# BMS_STM32.net
KiCad netlist of a schematic drawn in Altium Designer
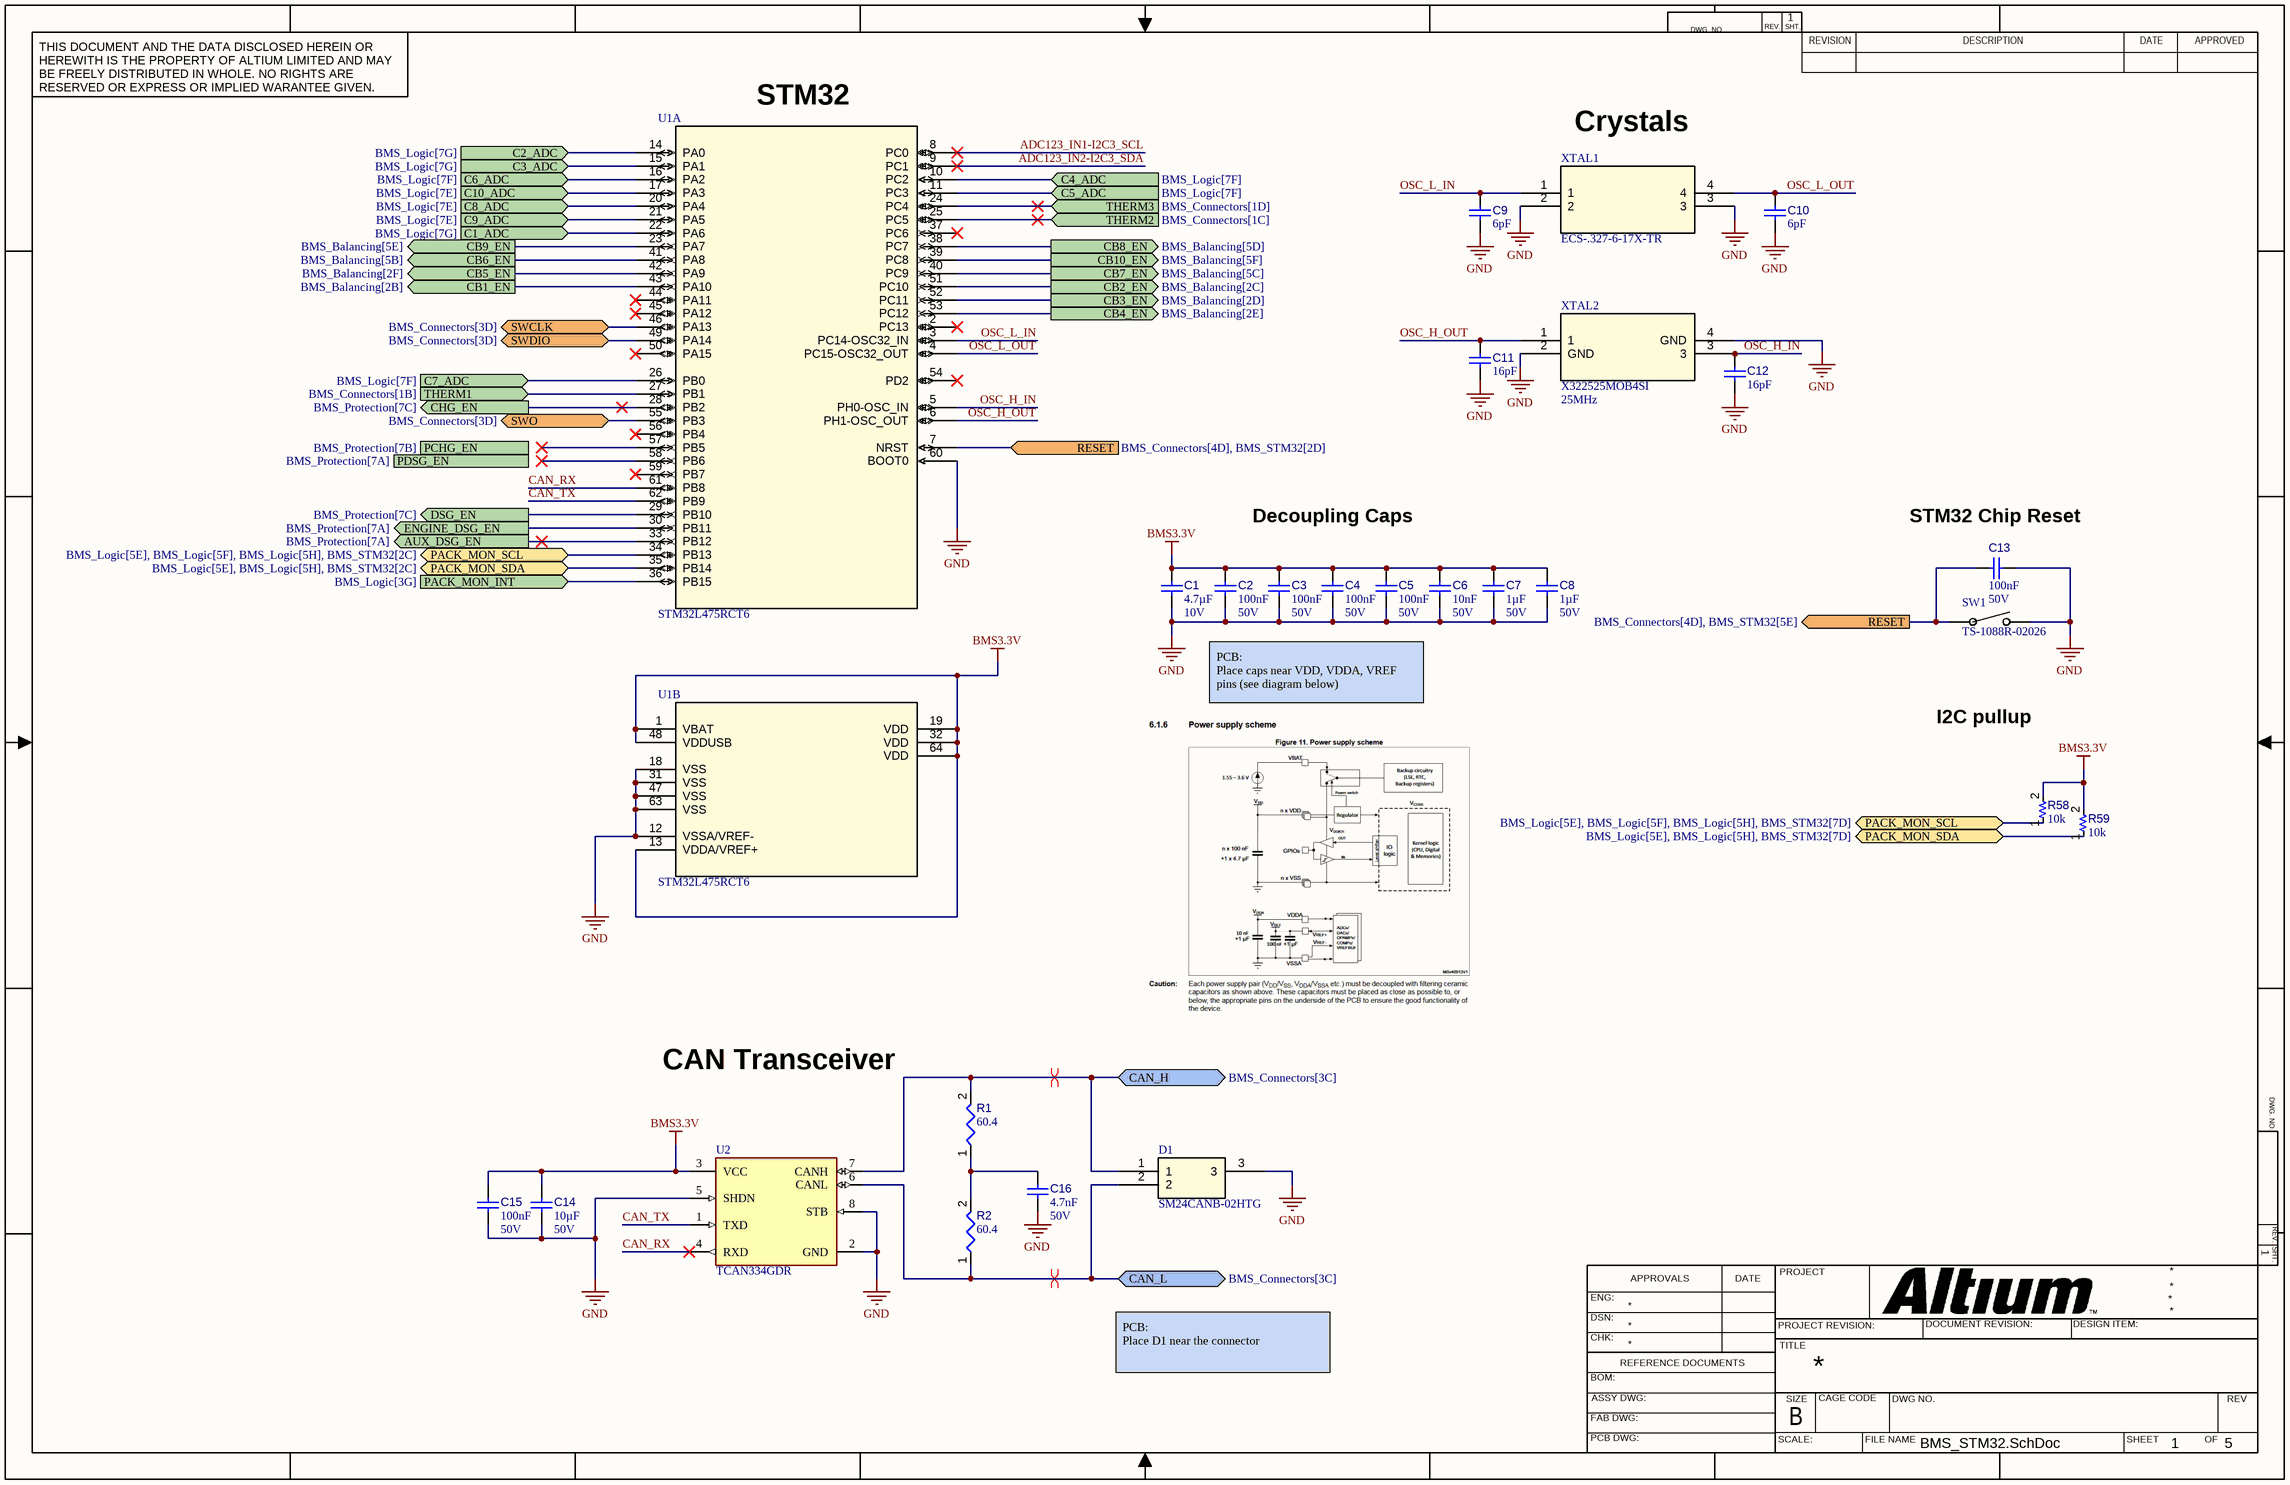
[diagram p0: BMS_STM32.SchDoc]

(export (version "E")
  (design (tool "Eeschema 10.0.6"))
  (components
    (comp (ref "C1")
      (value "4.7µF")
      (footprint "CAPC0603(1608)100_L")
      (description "Chip Capacitor, 4.7µF +/-20%, 10V, 0603, Thickness 1 mm")
      (fields
        (field (name "VOLTAGE RATING") "10V")
        (field (name "TOLERANCE") "10%")
        (field (name "Comment") "Capacitor 4.7µF +/-20% 10V 0603")
      )
      (libsource (lib "Caden Chan") (part "CAP-NP-2"))
    )
    (comp (ref "C2")
      (value "100nF")
      (footprint "CAPC0402(1005)60_L")
      (description "Chip Capacitor, 100nF +/-20%, 50V, 0402, Thickness 0.6 mm")
      (fields
        (field (name "VOLTAGE RATING") "50V")
        (field (name "TOLERANCE") "10%")
        (field (name "Comment") "Capacitor 100nF +/-20% 50V 0402")
      )
      (libsource (lib "Caden Chan") (part "CAP-NP-2"))
    )
    (comp (ref "C3")
      (value "100nF")
      (footprint "CAPC0402(1005)60_L")
      (description "Chip Capacitor, 100nF +/-20%, 50V, 0402, Thickness 0.6 mm")
      (fields
        (field (name "VOLTAGE RATING") "50V")
        (field (name "TOLERANCE") "10%")
        (field (name "Comment") "Capacitor 100nF +/-20% 50V 0402")
      )
      (libsource (lib "Caden Chan") (part "CAP-NP-2"))
    )
    (comp (ref "C4")
      (value "100nF")
      (footprint "CAPC0402(1005)60_L")
      (description "Chip Capacitor, 100nF +/-20%, 50V, 0402, Thickness 0.6 mm")
      (fields
        (field (name "VOLTAGE RATING") "50V")
        (field (name "TOLERANCE") "10%")
        (field (name "Comment") "Capacitor 100nF +/-20% 50V 0402")
      )
      (libsource (lib "Caden Chan") (part "CAP-NP-2"))
    )
    (comp (ref "C5")
      (value "100nF")
      (footprint "CAPC0402(1005)60_L")
      (description "Chip Capacitor, 100nF +/-20%, 50V, 0402, Thickness 0.6 mm")
      (fields
        (field (name "VOLTAGE RATING") "50V")
        (field (name "TOLERANCE") "10%")
        (field (name "Comment") "Capacitor 100nF +/-20% 50V 0402")
      )
      (libsource (lib "Caden Chan") (part "CAP-NP-2"))
    )
    (comp (ref "C6")
      (value "10nF")
      (footprint "CAPC0402(1005)60_L")
      (description "Chip Capacitor, 10nF +/-20%, 50V, 0402, Thickness 0.6 mm")
      (fields
        (field (name "VOLTAGE RATING") "50V")
        (field (name "TOLERANCE") "5%")
        (field (name "Comment") "Capacitor 10nF +/-20% 50V 0402")
      )
      (libsource (lib "Caden Chan") (part "CAP-NP-2"))
    )
    (comp (ref "C7")
      (value "1µF")
      (footprint "CAPC0603(1608)100_L")
      (description "Chip Capacitor, 1µF +/-40%, 50V, 0603, Thickness 1 mm")
      (fields
        (field (name "TOLERANCE") "10%")
        (field (name "VOLTAGE RATING") "50V")
        (field (name "Comment") "Capacitor 1µF +/-40% 50V 0603")
      )
      (libsource (lib "Caden Chan") (part "CAP-NP-2"))
    )
    (comp (ref "C8")
      (value "1µF")
      (footprint "CAPC0603(1608)100_L")
      (description "Chip Capacitor, 1µF +/-40%, 50V, 0603, Thickness 1 mm")
      (fields
        (field (name "TOLERANCE") "10%")
        (field (name "VOLTAGE RATING") "50V")
        (field (name "Comment") "Capacitor 1µF +/-40% 50V 0603")
      )
      (libsource (lib "Caden Chan") (part "CAP-NP-2"))
    )
    (comp (ref "C9")
      (value "6pF")
      (footprint "CAPC1709X04N")
      (fields (field (name "Comment") "Yageo CC0603CRNPO9BN6R0"))
      (libsource (lib "Caden Chan") (part "CAP-NP-2"))
    )
    (comp (ref "C10")
      (value "6pF")
      (footprint "CAPC1709X04N")
      (fields (field (name "Comment") "Yageo CC0603CRNPO9BN6R0"))
      (libsource (lib "Caden Chan") (part "CAP-NP-2"))
    )
    (comp (ref "C11")
      (value "16pF")
      (footprint "CAPC1709X04N")
      (description "Multilayer Ceramic Capacitor, 16 pF, 50 V, ± 5%, C0G (NP0), 0603 [1608 Metric]")
      (fields (field (name "Comment") "Yageo CC0603JRNPO9BN160"))
      (libsource (lib "Caden Chan") (part "CAP-NP-2"))
    )
    (comp (ref "C12")
      (value "16pF")
      (footprint "CAPC1709X04N")
      (description "Multilayer Ceramic Capacitor, 16 pF, 50 V, ± 5%, C0G (NP0), 0603 [1608 Metric]")
      (fields (field (name "Comment") "Yageo CC0603JRNPO9BN160"))
      (libsource (lib "Caden Chan") (part "CAP-NP-2"))
    )
    (comp (ref "C13")
      (value "100nF")
      (footprint "CAPC0402(1005)60_L")
      (description "Chip Capacitor, 100nF +/-20%, 50V, 0402, Thickness 0.6 mm")
      (fields
        (field (name "VOLTAGE RATING") "50V")
        (field (name "TOLERANCE") "10%")
        (field (name "Comment") "Capacitor 100nF +/-20% 50V 0402")
      )
      (libsource (lib "Caden Chan") (part "CAP-NP-2"))
    )
    (comp (ref "C14")
      (value "10µF")
      (footprint "CAPC0805(2012)145_L")
      (description "Chip Capacitor, 10µF +/-20%, 25V, 0805, Thickness 1.45 mm")
      (fields
        (field (name "VOLTAGE RATING") "50V")
        (field (name "TOLERANCE") "10%")
        (field (name "Comment") "Samsung Electro-Mechanics CL21A106KBYQNNE")
      )
      (libsource (lib "Caden Chan") (part "CAP-NP-2"))
    )
    (comp (ref "C15")
      (value "100nF")
      (footprint "CAPC0402(1005)60_L")
      (description "Chip Capacitor, 100nF +/-20%, 50V, 0402, Thickness 0.6 mm")
      (fields
        (field (name "VOLTAGE RATING") "50V")
        (field (name "TOLERANCE") "10%")
        (field (name "Comment") "Capacitor 100nF +/-20% 50V 0402")
      )
      (libsource (lib "Caden Chan") (part "CAP-NP-2"))
    )
    (comp (ref "C16")
      (value "4.7nF")
      (footprint "CAPC1709X04N")
      (fields (field (name "VOLTAGE RATING") "50V") (field (name "Comment") "yageo CC0603KRX7R9BB472"))
      (libsource (lib "Caden Chan") (part "CAP-NP-2"))
    )
    (comp (ref "D1")
      (value "SM24CANB-02HTG")
      (footprint "SOT23-3_SM24CANB-02HTG_LTF")
      (description "No Description Available")
      (fields (field (name "COPYRIGHT") "Copyright (C) 2025 Ultra Librarian. All rights reserved."))
      (libsource (lib "Caden Chan") (part "SM24CANB-02HTG"))
    )
    (comp (ref "R1")
      (value "60.4")
      (footprint "RESC1709X04N")
      (fields
        (field (name "TOLERANCE") "1%")
        (field (name "POWER") "100mW")
        (field (name "Comment") "yageo RC0603FR-0760R4L")
      )
      (libsource (lib "Caden Chan") (part "RES-2"))
    )
    (comp (ref "R2")
      (value "60.4")
      (footprint "RESC1709X04N")
      (fields
        (field (name "TOLERANCE") "1%")
        (field (name "POWER") "100mW")
        (field (name "Comment") "yageo RC0603FR-0760R4L")
      )
      (libsource (lib "Caden Chan") (part "RES-2"))
    )
    (comp (ref "R58")
      (value "10k")
      (footprint "RESC0402(1005)_L")
      (description "100R 0.063W 1% 0402 (1005 Metric)  SMD")
      (fields (field (name "TOLERANCE") "1%") (field (name "POWER") "63mW"))
      (libsource (lib "Caden Chan") (part "100R2F"))
    )
    (comp (ref "R59")
      (value "10k")
      (footprint "RESC0402(1005)_L")
      (description "100R 0.063W 1% 0402 (1005 Metric)  SMD")
      (fields (field (name "TOLERANCE") "1%") (field (name "POWER") "63mW"))
      (libsource (lib "Caden Chan") (part "100R2F"))
    )
    (comp (ref "SW1")
      (value "TS-1088R-02026")
      (footprint "SW_TS-1088R-02026_XNP")
      (description "No Description Available")
      (fields (field (name "COPYRIGHT") "Copyright (C) 2025 Ultra Librarian. All rights reserved."))
      (libsource (lib "Caden Chan") (part "TS-1088R-02026"))
    )
    (comp (ref "U1")
      (value "STM32L475RCT6")
      (footprint "LQFP64-10x10mm")
      (description "Ultra-low-power with FPU Arm Cortex-M4 MCU 80 MHz with 256 Kbytes of Flash memory, USB OTG, DFSDM")
      (fields (field (name "COPYRIGHT") "Copyright (C) 2025 Ultra Librarian. All rights reserved."))
      (libsource (lib "Caden Chan") (part "STM32L475RCT6"))
    )
    (comp (ref "U2")
      (value "TCAN334GDR")
      (footprint "FP-D0008A-IPC_B")
      (description "Interface Circuit, PDSO8")
      (libsource (lib "Caden Chan") (part "5621f34e3963f16c2984a53bd88c479"))
    )
    (comp (ref "XTAL1")
      (value "ECS-.327-6-17X-TR")
      (footprint "XTAL_7X-TR_ECS")
      (description "No Description Available")
      (fields (field (name "COPYRIGHT") "Copyright (C) 2025 Ultra Librarian. All rights reserved."))
      (libsource (lib "Caden Chan") (part "ECS-.327-6-17X-TR"))
    )
    (comp (ref "XTAL2")
      (value "X322525MOB4SI")
      (footprint "SMT_MOB4SI_YXC")
      (description "No Description Available")
      (fields
        (field (name "FREQUENCY") "25MHz")
        (field (name "COPYRIGHT") "Copyright (C) 2025 Ultra Librarian. All rights reserved.")
      )
      (libsource (lib "Caden Chan") (part "X322525MOB4SI"))
    )
  )
  (nets
    (net (code "1") (name "/ADC123_IN1-I2C3_SCL") (class "Default")
      (node (ref "U1") (pin "8") (pinfunction "PC0_8") (pintype "bidirectional+no_connect"))
    )
    (net (code "2") (name "/ADC123_IN2-I2C3_SDA") (class "Default")
      (node (ref "U1") (pin "9") (pinfunction "PC1_9") (pintype "bidirectional+no_connect"))
    )
    (net (code "3") (name "/AUX_DSG_EN") (class "Default")
      (node (ref "U1") (pin "33") (pinfunction "PB12_33") (pintype "output"))
    )
    (net (code "4") (name "/C1_ADC") (class "Default")
      (node (ref "U1") (pin "22") (pinfunction "PA6_22") (pintype "input"))
    )
    (net (code "5") (name "/C2_ADC") (class "Default")
      (node (ref "U1") (pin "14") (pinfunction "PA0_14") (pintype "input"))
    )
    (net (code "6") (name "/C3_ADC") (class "Default")
      (node (ref "U1") (pin "15") (pinfunction "PA1_15") (pintype "input"))
    )
    (net (code "7") (name "/C4_ADC") (class "Default")
      (node (ref "U1") (pin "10") (pinfunction "PC2_10") (pintype "input"))
    )
    (net (code "8") (name "/C5_ADC") (class "Default")
      (node (ref "U1") (pin "11") (pinfunction "PC3_11") (pintype "input"))
    )
    (net (code "9") (name "/C6_ADC") (class "Default")
      (node (ref "U1") (pin "16") (pinfunction "PA2_16") (pintype "input"))
    )
    (net (code "10") (name "/C7_ADC") (class "Default")
      (node (ref "U1") (pin "26") (pinfunction "PB0_26") (pintype "input"))
    )
    (net (code "11") (name "/C8_ADC") (class "Default")
      (node (ref "U1") (pin "20") (pinfunction "PA4_20") (pintype "input"))
    )
    (net (code "12") (name "/C9_ADC") (class "Default")
      (node (ref "U1") (pin "21") (pinfunction "PA5_21") (pintype "input"))
    )
    (net (code "13") (name "/C10_ADC") (class "Default")
      (node (ref "U1") (pin "17") (pinfunction "PA3_17") (pintype "input"))
    )
    (net (code "14") (name "/CAN_H") (class "Default")
      (node (ref "D1") (pin "1") (pinfunction "1_1") (pintype "passive"))
      (node (ref "R1") (pin "2") (pinfunction "2_2") (pintype "passive"))
      (node (ref "U2") (pin "7") (pinfunction "CANH_7") (pintype "bidirectional"))
    )
    (net (code "15") (name "/CAN_L") (class "Default")
      (node (ref "D1") (pin "2") (pinfunction "2_2") (pintype "passive"))
      (node (ref "R2") (pin "1") (pinfunction "1_1") (pintype "passive"))
      (node (ref "U2") (pin "6") (pinfunction "CANL_6") (pintype "bidirectional"))
    )
    (net (code "16") (name "/CAN_RX") (class "Default")
      (node (ref "U1") (pin "61") (pinfunction "PB8_61") (pintype "bidirectional"))
      (node (ref "U2") (pin "4") (pinfunction "RXD_4") (pintype "output"))
    )
    (net (code "17") (name "/CAN_TX") (class "Default")
      (node (ref "U1") (pin "62") (pinfunction "PB9_62") (pintype "bidirectional"))
      (node (ref "U2") (pin "1") (pinfunction "TXD_1") (pintype "input"))
    )
    (net (code "18") (name "/CB1_EN") (class "Default")
      (node (ref "U1") (pin "43") (pinfunction "PA10_43") (pintype "output"))
    )
    (net (code "19") (name "/CB2_EN") (class "Default")
      (node (ref "U1") (pin "51") (pinfunction "PC10_51") (pintype "output"))
    )
    (net (code "20") (name "/CB3_EN") (class "Default")
      (node (ref "U1") (pin "52") (pinfunction "PC11_52") (pintype "output"))
    )
    (net (code "21") (name "/CB4_EN") (class "Default")
      (node (ref "U1") (pin "53") (pinfunction "PC12_53") (pintype "output"))
    )
    (net (code "22") (name "/CB5_EN") (class "Default")
      (node (ref "U1") (pin "42") (pinfunction "PA9_42") (pintype "output"))
    )
    (net (code "23") (name "/CB6_EN") (class "Default")
      (node (ref "U1") (pin "41") (pinfunction "PA8_41") (pintype "output"))
    )
    (net (code "24") (name "/CB7_EN") (class "Default")
      (node (ref "U1") (pin "40") (pinfunction "PC9_40") (pintype "output"))
    )
    (net (code "25") (name "/CB8_EN") (class "Default")
      (node (ref "U1") (pin "38") (pinfunction "PC7_38") (pintype "output"))
    )
    (net (code "26") (name "/CB9_EN") (class "Default")
      (node (ref "U1") (pin "23") (pinfunction "PA7_23") (pintype "output"))
    )
    (net (code "27") (name "/CB10_EN") (class "Default")
      (node (ref "U1") (pin "39") (pinfunction "PC8_39") (pintype "output"))
    )
    (net (code "28") (name "/CHG_EN") (class "Default")
      (node (ref "U1") (pin "28") (pinfunction "PB2_28") (pintype "bidirectional"))
    )
    (net (code "29") (name "/DSG_EN") (class "Default")
      (node (ref "U1") (pin "29") (pinfunction "PB10_29") (pintype "output"))
    )
    (net (code "30") (name "/ENGINE_DSG_EN") (class "Default")
      (node (ref "U1") (pin "30") (pinfunction "PB11_30") (pintype "output"))
    )
    (net (code "31") (name "/OSC_H_IN") (class "Default")
      (node (ref "C12") (pin "2") (pinfunction "2_2") (pintype "passive"))
      (node (ref "U1") (pin "5") (pinfunction "PH0-OSC_IN_5") (pintype "bidirectional"))
      (node (ref "XTAL2") (pin "3") (pinfunction "3_3") (pintype "passive"))
    )
    (net (code "32") (name "/OSC_H_OUT") (class "Default")
      (node (ref "C11") (pin "1") (pinfunction "1_1") (pintype "passive"))
      (node (ref "U1") (pin "6") (pinfunction "PH1-OSC_OUT_6") (pintype "bidirectional"))
      (node (ref "XTAL2") (pin "1") (pinfunction "1_1") (pintype "passive"))
    )
    (net (code "33") (name "/OSC_L_IN") (class "Default")
      (node (ref "C9") (pin "1") (pinfunction "1_1") (pintype "passive"))
      (node (ref "U1") (pin "3") (pinfunction "PC14-OSC32_IN_3") (pintype "bidirectional"))
      (node (ref "XTAL1") (pin "1") (pinfunction "1_1") (pintype "passive"))
    )
    (net (code "34") (name "/OSC_L_OUT") (class "Default")
      (node (ref "C10") (pin "1") (pinfunction "1_1") (pintype "passive"))
      (node (ref "U1") (pin "4") (pinfunction "PC15-OSC32_OUT_4") (pintype "bidirectional"))
      (node (ref "XTAL1") (pin "4") (pinfunction "4_4") (pintype "passive"))
    )
    (net (code "35") (name "/PACK_MON_INT") (class "Default")
      (node (ref "U1") (pin "36") (pinfunction "PB15_36") (pintype "input"))
    )
    (net (code "36") (name "/PACK_MON_SCL") (class "Default")
      (node (ref "R58") (pin "1") (pinfunction "1_1") (pintype "passive"))
      (node (ref "U1") (pin "34") (pinfunction "PB13_34") (pintype "bidirectional"))
    )
    (net (code "37") (name "/PACK_MON_SDA") (class "Default")
      (node (ref "R59") (pin "1") (pinfunction "1_1") (pintype "passive"))
      (node (ref "U1") (pin "35") (pinfunction "PB14_35") (pintype "bidirectional"))
    )
    (net (code "40") (name "/RESET") (class "Default")
      (node (ref "C13") (pin "2") (pinfunction "2_2") (pintype "passive"))
      (node (ref "SW1") (pin "1") (pinfunction "1_1") (pintype "passive"))
      (node (ref "U1") (pin "7") (pinfunction "NRST_7") (pintype "input"))
    )
    (net (code "41") (name "/SWCLK") (class "Default")
      (node (ref "U1") (pin "46") (pinfunction "PA13_46") (pintype "bidirectional"))
    )
    (net (code "42") (name "/SWDIO") (class "Default")
      (node (ref "U1") (pin "49") (pinfunction "PA14_49") (pintype "bidirectional"))
    )
    (net (code "43") (name "/SWO") (class "Default")
      (node (ref "U1") (pin "55") (pinfunction "PB3_55") (pintype "bidirectional"))
    )
    (net (code "44") (name "/THERM1") (class "Default")
      (node (ref "U1") (pin "27") (pinfunction "PB1_27") (pintype "input"))
    )
    (net (code "45") (name "/THERM2") (class "Default")
      (node (ref "U1") (pin "25") (pinfunction "PC5_25") (pintype "bidirectional"))
    )
    (net (code "46") (name "/THERM3") (class "Default")
      (node (ref "U1") (pin "24") (pinfunction "PC4_24") (pintype "bidirectional"))
    )
    (net (code "47") (name "BMS3.3V") (class "Default")
      (node (ref "C1") (pin "1") (pinfunction "1_1") (pintype "passive"))
      (node (ref "C14") (pin "1") (pinfunction "1_1") (pintype "passive"))
      (node (ref "C15") (pin "1") (pinfunction "1_1") (pintype "passive"))
      (node (ref "C2") (pin "2") (pinfunction "2_2") (pintype "passive"))
      (node (ref "C3") (pin "2") (pinfunction "2_2") (pintype "passive"))
      (node (ref "C4") (pin "2") (pinfunction "2_2") (pintype "passive"))
      (node (ref "C5") (pin "2") (pinfunction "2_2") (pintype "passive"))
      (node (ref "C6") (pin "1") (pinfunction "1_1") (pintype "passive"))
      (node (ref "C7") (pin "1") (pinfunction "1_1") (pintype "passive"))
      (node (ref "C8") (pin "1") (pinfunction "1_1") (pintype "passive"))
      (node (ref "R58") (pin "2") (pinfunction "2_2") (pintype "passive"))
      (node (ref "R59") (pin "2") (pinfunction "2_2") (pintype "passive"))
      (node (ref "U1") (pin "1") (pinfunction "VBAT_1") (pintype "power_in"))
      (node (ref "U1") (pin "13") (pinfunction "VDDA/VREF+_13") (pintype "power_in"))
      (node (ref "U1") (pin "19") (pinfunction "VDD_19") (pintype "power_in"))
      (node (ref "U1") (pin "32") (pinfunction "VDD_32") (pintype "power_in"))
      (node (ref "U1") (pin "48") (pinfunction "VDDUSB_48") (pintype "power_in"))
      (node (ref "U1") (pin "64") (pinfunction "VDD_64") (pintype "power_in"))
      (node (ref "U2") (pin "3") (pinfunction "VCC_3") (pintype "power_in"))
    )
    (net (code "48") (name "GND") (class "Default")
      (node (ref "C1") (pin "2") (pinfunction "2_2") (pintype "passive"))
      (node (ref "C10") (pin "2") (pinfunction "2_2") (pintype "passive"))
      (node (ref "C11") (pin "2") (pinfunction "2_2") (pintype "passive"))
      (node (ref "C12") (pin "1") (pinfunction "1_1") (pintype "passive"))
      (node (ref "C13") (pin "1") (pinfunction "1_1") (pintype "passive"))
      (node (ref "C14") (pin "2") (pinfunction "2_2") (pintype "passive"))
      (node (ref "C15") (pin "2") (pinfunction "2_2") (pintype "passive"))
      (node (ref "C16") (pin "2") (pinfunction "2_2") (pintype "passive"))
      (node (ref "C2") (pin "1") (pinfunction "1_1") (pintype "passive"))
      (node (ref "C3") (pin "1") (pinfunction "1_1") (pintype "passive"))
      (node (ref "C4") (pin "1") (pinfunction "1_1") (pintype "passive"))
      (node (ref "C5") (pin "1") (pinfunction "1_1") (pintype "passive"))
      (node (ref "C6") (pin "2") (pinfunction "2_2") (pintype "passive"))
      (node (ref "C7") (pin "2") (pinfunction "2_2") (pintype "passive"))
      (node (ref "C8") (pin "2") (pinfunction "2_2") (pintype "passive"))
      (node (ref "C9") (pin "2") (pinfunction "2_2") (pintype "passive"))
      (node (ref "D1") (pin "3") (pinfunction "3_3") (pintype "passive"))
      (node (ref "SW1") (pin "2") (pinfunction "2_2") (pintype "passive"))
      (node (ref "U1") (pin "12") (pinfunction "VSSA/VREF-_12") (pintype "power_in"))
      (node (ref "U1") (pin "18") (pinfunction "VSS_18") (pintype "power_in"))
      (node (ref "U1") (pin "31") (pinfunction "VSS_31") (pintype "power_in"))
      (node (ref "U1") (pin "47") (pinfunction "VSS_47") (pintype "power_in"))
      (node (ref "U1") (pin "60") (pinfunction "BOOT0_60") (pintype "input"))
      (node (ref "U1") (pin "63") (pinfunction "VSS_63") (pintype "power_in"))
      (node (ref "U2") (pin "2") (pinfunction "GND_2") (pintype "power_in"))
      (node (ref "U2") (pin "5") (pinfunction "SHDN_5") (pintype "input"))
      (node (ref "U2") (pin "8") (pinfunction "STB_8") (pintype "input"))
      (node (ref "XTAL1") (pin "2") (pinfunction "2_2") (pintype "passive"))
      (node (ref "XTAL1") (pin "3") (pinfunction "3_3") (pintype "passive"))
      (node (ref "XTAL2") (pin "2") (pinfunction "GND_2") (pintype "power_in"))
      (node (ref "XTAL2") (pin "4") (pinfunction "GND_4") (pintype "power_in"))
    )
    (net (code "49") (name "Net-(C16-Pad1)") (class "Default")
      (node (ref "C16") (pin "1") (pinfunction "1_1") (pintype "passive"))
      (node (ref "R1") (pin "1") (pinfunction "1_1") (pintype "passive"))
      (node (ref "R2") (pin "2") (pinfunction "2_2") (pintype "passive"))
    )
    (net (code "50") (name "unconnected-(U1A-PA11-Pad44)") (class "Default")
      (node (ref "U1") (pin "44") (pinfunction "PA11_44") (pintype "bidirectional+no_connect"))
    )
    (net (code "51") (name "unconnected-(U1A-PA12-Pad45)") (class "Default")
      (node (ref "U1") (pin "45") (pinfunction "PA12_45") (pintype "bidirectional+no_connect"))
    )
    (net (code "52") (name "unconnected-(U1A-PA15-Pad50)") (class "Default")
      (node (ref "U1") (pin "50") (pinfunction "PA15_50") (pintype "bidirectional+no_connect"))
    )
    (net (code "53") (name "unconnected-(U1A-PB4-Pad56)") (class "Default")
      (node (ref "U1") (pin "56") (pinfunction "PB4_56") (pintype "bidirectional+no_connect"))
    )
    (net (code "54") (name "unconnected-(U1A-PB5-Pad57)") (class "Default")
      (node (ref "U1") (pin "57") (pinfunction "PB5_57") (pintype "output+no_connect"))
    )
    (net (code "55") (name "unconnected-(U1A-PB6-Pad58)") (class "Default")
      (node (ref "U1") (pin "58") (pinfunction "PB6_58") (pintype "output+no_connect"))
    )
    (net (code "56") (name "unconnected-(U1A-PB7-Pad59)") (class "Default")
      (node (ref "U1") (pin "59") (pinfunction "PB7_59") (pintype "output+no_connect"))
    )
    (net (code "57") (name "unconnected-(U1A-PC6-Pad37)") (class "Default")
      (node (ref "U1") (pin "37") (pinfunction "PC6_37") (pintype "output+no_connect"))
    )
    (net (code "58") (name "unconnected-(U1A-PC13-Pad2)") (class "Default")
      (node (ref "U1") (pin "2") (pinfunction "PC13_2") (pintype "bidirectional+no_connect"))
    )
    (net (code "59") (name "unconnected-(U1A-PD2-Pad54)") (class "Default")
      (node (ref "U1") (pin "54") (pinfunction "PD2_54") (pintype "bidirectional+no_connect"))
    )
  )
)
